# Umbilical104.net
KiCad netlist of a schematic drawn in Altium Designer
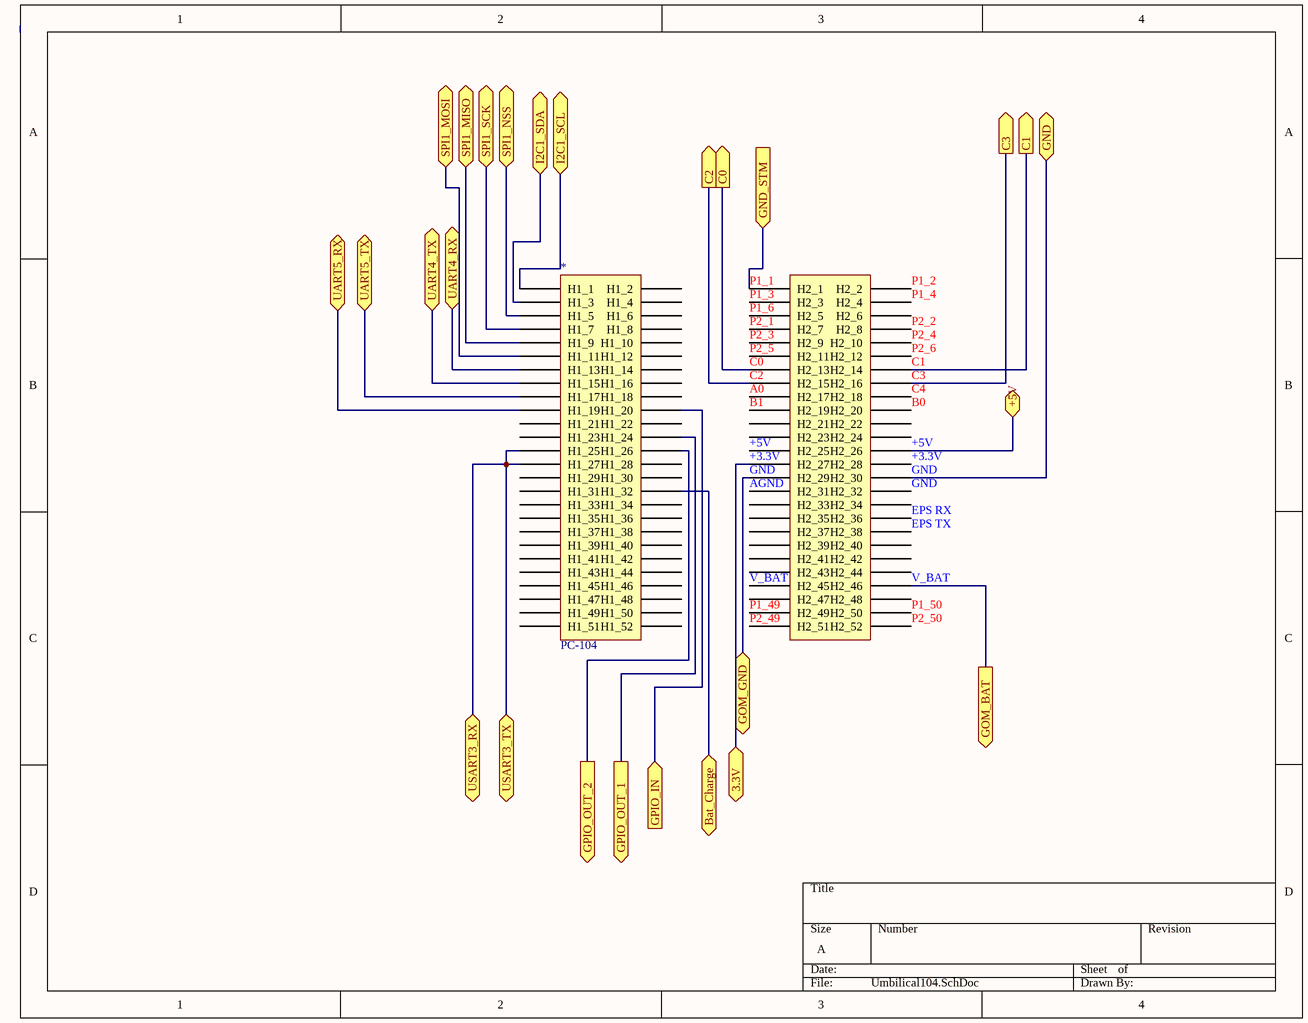
[diagram p0: Umbilical104.SchDoc]

(export (version "E")
  (design (tool "Eeschema 10.0.6"))
  (components
    (comp (ref "*")
      (value "PC-104")
      (footprint "PC-104FOOTPRINT")
      (libsource (lib "AdapterBoard") (part "PC-104"))
    )
  )
  (nets
    (net (code "1") (name "/+3.3V") (class "Default")
      (node (ref "*") (pin "H2_27") (pinfunction "H2_27_H2_27") (pintype "passive"))
      (node (ref "*") (pin "H2_28") (pinfunction "H2_28_H2_28") (pintype "passive"))
    )
    (net (code "2") (name "/+5V") (class "Default")
      (node (ref "*") (pin "H2_25") (pinfunction "H2_25_H2_25") (pintype "passive"))
      (node (ref "*") (pin "H2_26") (pinfunction "H2_26_H2_26") (pintype "passive"))
    )
    (net (code "3") (name "/A0") (class "Default")
      (node (ref "*") (pin "H2_17") (pinfunction "H2_17_H2_17") (pintype "passive"))
    )
    (net (code "4") (name "/AGND") (class "Default")
      (node (ref "*") (pin "H2_31") (pinfunction "H2_31_H2_31") (pintype "passive"))
    )
    (net (code "5") (name "/B0") (class "Default")
      (node (ref "*") (pin "H2_20") (pinfunction "H2_20_H2_20") (pintype "passive"))
    )
    (net (code "6") (name "/B1") (class "Default")
      (node (ref "*") (pin "H2_19") (pinfunction "H2_19_H2_19") (pintype "passive"))
    )
    (net (code "7") (name "/Bat_Charge") (class "Default")
      (node (ref "*") (pin "H1_32") (pinfunction "H1_32_H1_32") (pintype "passive"))
    )
    (net (code "8") (name "/C0") (class "Default")
      (node (ref "*") (pin "H2_13") (pinfunction "H2_13_H2_13") (pintype "passive"))
    )
    (net (code "9") (name "/C1") (class "Default")
      (node (ref "*") (pin "H2_14") (pinfunction "H2_14_H2_14") (pintype "passive"))
    )
    (net (code "10") (name "/C2") (class "Default")
      (node (ref "*") (pin "H2_15") (pinfunction "H2_15_H2_15") (pintype "passive"))
    )
    (net (code "11") (name "/C3") (class "Default")
      (node (ref "*") (pin "H2_16") (pinfunction "H2_16_H2_16") (pintype "passive"))
    )
    (net (code "12") (name "/C4") (class "Default")
      (node (ref "*") (pin "H2_18") (pinfunction "H2_18_H2_18") (pintype "passive"))
    )
    (net (code "13") (name "/EPS RX") (class "Default")
      (node (ref "*") (pin "H2_36") (pinfunction "H2_36_H2_36") (pintype "passive"))
    )
    (net (code "14") (name "/EPS TX") (class "Default")
      (node (ref "*") (pin "H2_38") (pinfunction "H2_38_H2_38") (pintype "passive"))
    )
    (net (code "15") (name "/GND") (class "Default")
      (node (ref "*") (pin "H2_29") (pinfunction "H2_29_H2_29") (pintype "passive"))
      (node (ref "*") (pin "H2_30") (pinfunction "H2_30_H2_30") (pintype "passive"))
      (node (ref "*") (pin "H2_32") (pinfunction "H2_32_H2_32") (pintype "passive"))
    )
    (net (code "16") (name "/GPIO_IN") (class "Default")
      (node (ref "*") (pin "H1_20") (pinfunction "H1_20_H1_20") (pintype "passive"))
    )
    (net (code "17") (name "/GPIO_OUT_1") (class "Default")
      (node (ref "*") (pin "H1_24") (pinfunction "H1_24_H1_24") (pintype "passive"))
    )
    (net (code "18") (name "/GPIO_OUT_2") (class "Default")
      (node (ref "*") (pin "H1_26") (pinfunction "H1_26_H1_26") (pintype "passive"))
    )
    (net (code "19") (name "/I2C1_SCL") (class "Default")
      (node (ref "*") (pin "H1_1") (pinfunction "H1_1_H1_1") (pintype "passive"))
    )
    (net (code "20") (name "/I2C1_SDA") (class "Default")
      (node (ref "*") (pin "H1_3") (pinfunction "H1_3_H1_3") (pintype "passive"))
    )
    (net (code "21") (name "/P1_1") (class "Default")
      (node (ref "*") (pin "H2_1") (pinfunction "H2_1_H2_1") (pintype "passive"))
    )
    (net (code "22") (name "/P1_2") (class "Default")
      (node (ref "*") (pin "H2_2") (pinfunction "H2_2_H2_2") (pintype "passive"))
    )
    (net (code "23") (name "/P1_3") (class "Default")
      (node (ref "*") (pin "H2_3") (pinfunction "H2_3_H2_3") (pintype "passive"))
    )
    (net (code "24") (name "/P1_4") (class "Default")
      (node (ref "*") (pin "H2_4") (pinfunction "H2_4_H2_4") (pintype "passive"))
    )
    (net (code "25") (name "/P1_6") (class "Default")
      (node (ref "*") (pin "H2_5") (pinfunction "H2_5_H2_5") (pintype "passive"))
    )
    (net (code "26") (name "/P1_49") (class "Default")
      (node (ref "*") (pin "H2_49") (pinfunction "H2_49_H2_49") (pintype "passive"))
    )
    (net (code "27") (name "/P1_50") (class "Default")
      (node (ref "*") (pin "H2_50") (pinfunction "H2_50_H2_50") (pintype "passive"))
    )
    (net (code "28") (name "/P2_1") (class "Default")
      (node (ref "*") (pin "H2_7") (pinfunction "H2_7_H2_7") (pintype "passive"))
    )
    (net (code "29") (name "/P2_2") (class "Default")
      (node (ref "*") (pin "H2_8") (pinfunction "H2_8_H2_8") (pintype "passive"))
    )
    (net (code "30") (name "/P2_3") (class "Default")
      (node (ref "*") (pin "H2_9") (pinfunction "H2_9_H2_9") (pintype "passive"))
    )
    (net (code "31") (name "/P2_4") (class "Default")
      (node (ref "*") (pin "H2_10") (pinfunction "H2_10_H2_10") (pintype "passive"))
    )
    (net (code "32") (name "/P2_5") (class "Default")
      (node (ref "*") (pin "H2_11") (pinfunction "H2_11_H2_11") (pintype "passive"))
    )
    (net (code "33") (name "/P2_6") (class "Default")
      (node (ref "*") (pin "H2_12") (pinfunction "H2_12_H2_12") (pintype "passive"))
    )
    (net (code "34") (name "/P2_49") (class "Default")
      (node (ref "*") (pin "H2_51") (pinfunction "H2_51_H2_51") (pintype "passive"))
    )
    (net (code "35") (name "/P2_50") (class "Default")
      (node (ref "*") (pin "H2_52") (pinfunction "H2_52_H2_52") (pintype "passive"))
    )
    (net (code "36") (name "/SPI1_MISO") (class "Default")
      (node (ref "*") (pin "H1_9") (pinfunction "H1_9_H1_9") (pintype "passive"))
    )
    (net (code "37") (name "/SPI1_MOSI") (class "Default")
      (node (ref "*") (pin "H1_11") (pinfunction "H1_11_H1_11") (pintype "passive"))
    )
    (net (code "38") (name "/SPI1_NSS") (class "Default")
      (node (ref "*") (pin "H1_5") (pinfunction "H1_5_H1_5") (pintype "passive"))
    )
    (net (code "39") (name "/SPI1_SCK") (class "Default")
      (node (ref "*") (pin "H1_7") (pinfunction "H1_7_H1_7") (pintype "passive"))
    )
    (net (code "40") (name "/UART4_RX") (class "Default")
      (node (ref "*") (pin "H1_13") (pinfunction "H1_13_H1_13") (pintype "passive"))
    )
    (net (code "41") (name "/UART4_TX") (class "Default")
      (node (ref "*") (pin "H1_15") (pinfunction "H1_15_H1_15") (pintype "passive"))
    )
    (net (code "42") (name "/UART5_RX") (class "Default")
      (node (ref "*") (pin "H1_19") (pinfunction "H1_19_H1_19") (pintype "passive"))
    )
    (net (code "43") (name "/UART5_TX") (class "Default")
      (node (ref "*") (pin "H1_17") (pinfunction "H1_17_H1_17") (pintype "passive"))
    )
    (net (code "44") (name "/USART3_RX") (class "Default")
      (node (ref "*") (pin "H1_25") (pinfunction "H1_25_H1_25") (pintype "passive"))
      (node (ref "*") (pin "H1_27") (pinfunction "H1_27_H1_27") (pintype "passive"))
    )
    (net (code "45") (name "/V_BAT") (class "Default")
      (node (ref "*") (pin "H2_45") (pinfunction "H2_45_H2_45") (pintype "passive"))
      (node (ref "*") (pin "H2_46") (pinfunction "H2_46_H2_46") (pintype "passive"))
    )
    (net (code "46") (name "unconnected-(*-PadH1_2)") (class "Default")
      (node (ref "*") (pin "H1_2") (pinfunction "H1_2_H1_2") (pintype "passive"))
    )
    (net (code "47") (name "unconnected-(*-PadH1_4)") (class "Default")
      (node (ref "*") (pin "H1_4") (pinfunction "H1_4_H1_4") (pintype "passive"))
    )
    (net (code "48") (name "unconnected-(*-PadH1_6)") (class "Default")
      (node (ref "*") (pin "H1_6") (pinfunction "H1_6_H1_6") (pintype "passive"))
    )
    (net (code "49") (name "unconnected-(*-PadH1_8)") (class "Default")
      (node (ref "*") (pin "H1_8") (pinfunction "H1_8_H1_8") (pintype "passive"))
    )
    (net (code "50") (name "unconnected-(*-PadH1_10)") (class "Default")
      (node (ref "*") (pin "H1_10") (pinfunction "H1_10_H1_10") (pintype "passive"))
    )
    (net (code "51") (name "unconnected-(*-PadH1_12)") (class "Default")
      (node (ref "*") (pin "H1_12") (pinfunction "H1_12_H1_12") (pintype "passive"))
    )
    (net (code "52") (name "unconnected-(*-PadH1_14)") (class "Default")
      (node (ref "*") (pin "H1_14") (pinfunction "H1_14_H1_14") (pintype "passive"))
    )
    (net (code "53") (name "unconnected-(*-PadH1_16)") (class "Default")
      (node (ref "*") (pin "H1_16") (pinfunction "H1_16_H1_16") (pintype "passive"))
    )
    (net (code "54") (name "unconnected-(*-PadH1_18)") (class "Default")
      (node (ref "*") (pin "H1_18") (pinfunction "H1_18_H1_18") (pintype "passive"))
    )
    (net (code "55") (name "unconnected-(*-PadH1_21)") (class "Default")
      (node (ref "*") (pin "H1_21") (pinfunction "H1_21_H1_21") (pintype "passive"))
    )
    (net (code "56") (name "unconnected-(*-PadH1_22)") (class "Default")
      (node (ref "*") (pin "H1_22") (pinfunction "H1_22_H1_22") (pintype "passive"))
    )
    (net (code "57") (name "unconnected-(*-PadH1_23)") (class "Default")
      (node (ref "*") (pin "H1_23") (pinfunction "H1_23_H1_23") (pintype "passive"))
    )
    (net (code "58") (name "unconnected-(*-PadH1_28)") (class "Default")
      (node (ref "*") (pin "H1_28") (pinfunction "H1_28_H1_28") (pintype "passive"))
    )
    (net (code "59") (name "unconnected-(*-PadH1_29)") (class "Default")
      (node (ref "*") (pin "H1_29") (pinfunction "H1_29_H1_29") (pintype "passive"))
    )
    (net (code "60") (name "unconnected-(*-PadH1_30)") (class "Default")
      (node (ref "*") (pin "H1_30") (pinfunction "H1_30_H1_30") (pintype "passive"))
    )
    (net (code "61") (name "unconnected-(*-PadH1_31)") (class "Default")
      (node (ref "*") (pin "H1_31") (pinfunction "H1_31_H1_31") (pintype "passive"))
    )
    (net (code "62") (name "unconnected-(*-PadH1_33)") (class "Default")
      (node (ref "*") (pin "H1_33") (pinfunction "H1_33_H1_33") (pintype "passive"))
    )
    (net (code "63") (name "unconnected-(*-PadH1_34)") (class "Default")
      (node (ref "*") (pin "H1_34") (pinfunction "H1_34_H1_34") (pintype "passive"))
    )
    (net (code "64") (name "unconnected-(*-PadH1_35)") (class "Default")
      (node (ref "*") (pin "H1_35") (pinfunction "H1_35_H1_35") (pintype "passive"))
    )
    (net (code "65") (name "unconnected-(*-PadH1_36)") (class "Default")
      (node (ref "*") (pin "H1_36") (pinfunction "H1_36_H1_36") (pintype "passive"))
    )
    (net (code "66") (name "unconnected-(*-PadH1_37)") (class "Default")
      (node (ref "*") (pin "H1_37") (pinfunction "H1_37_H1_37") (pintype "passive"))
    )
    (net (code "67") (name "unconnected-(*-PadH1_38)") (class "Default")
      (node (ref "*") (pin "H1_38") (pinfunction "H1_38_H1_38") (pintype "passive"))
    )
    (net (code "68") (name "unconnected-(*-PadH1_39)") (class "Default")
      (node (ref "*") (pin "H1_39") (pinfunction "H1_39_H1_39") (pintype "passive"))
    )
    (net (code "69") (name "unconnected-(*-PadH1_40)") (class "Default")
      (node (ref "*") (pin "H1_40") (pinfunction "H1_40_H1_40") (pintype "passive"))
    )
    (net (code "70") (name "unconnected-(*-PadH1_41)") (class "Default")
      (node (ref "*") (pin "H1_41") (pinfunction "H1_41_H1_41") (pintype "passive"))
    )
    (net (code "71") (name "unconnected-(*-PadH1_42)") (class "Default")
      (node (ref "*") (pin "H1_42") (pinfunction "H1_42_H1_42") (pintype "passive"))
    )
    (net (code "72") (name "unconnected-(*-PadH1_43)") (class "Default")
      (node (ref "*") (pin "H1_43") (pinfunction "H1_43_H1_43") (pintype "passive"))
    )
    (net (code "73") (name "unconnected-(*-PadH1_44)") (class "Default")
      (node (ref "*") (pin "H1_44") (pinfunction "H1_44_H1_44") (pintype "passive"))
    )
    (net (code "74") (name "unconnected-(*-PadH1_45)") (class "Default")
      (node (ref "*") (pin "H1_45") (pinfunction "H1_45_H1_45") (pintype "passive"))
    )
    (net (code "75") (name "unconnected-(*-PadH1_46)") (class "Default")
      (node (ref "*") (pin "H1_46") (pinfunction "H1_46_H1_46") (pintype "passive"))
    )
    (net (code "76") (name "unconnected-(*-PadH1_47)") (class "Default")
      (node (ref "*") (pin "H1_47") (pinfunction "H1_47_H1_47") (pintype "passive"))
    )
    (net (code "77") (name "unconnected-(*-PadH1_48)") (class "Default")
      (node (ref "*") (pin "H1_48") (pinfunction "H1_48_H1_48") (pintype "passive"))
    )
    (net (code "78") (name "unconnected-(*-PadH1_49)") (class "Default")
      (node (ref "*") (pin "H1_49") (pinfunction "H1_49_H1_49") (pintype "passive"))
    )
    (net (code "79") (name "unconnected-(*-PadH1_50)") (class "Default")
      (node (ref "*") (pin "H1_50") (pinfunction "H1_50_H1_50") (pintype "passive"))
    )
    (net (code "80") (name "unconnected-(*-PadH1_51)") (class "Default")
      (node (ref "*") (pin "H1_51") (pinfunction "H1_51_H1_51") (pintype "passive"))
    )
    (net (code "81") (name "unconnected-(*-PadH1_52)") (class "Default")
      (node (ref "*") (pin "H1_52") (pinfunction "H1_52_H1_52") (pintype "passive"))
    )
    (net (code "82") (name "unconnected-(*-PadH2_6)") (class "Default")
      (node (ref "*") (pin "H2_6") (pinfunction "H2_6_H2_6") (pintype "passive"))
    )
    (net (code "83") (name "unconnected-(*-PadH2_21)") (class "Default")
      (node (ref "*") (pin "H2_21") (pinfunction "H2_21_H2_21") (pintype "passive"))
    )
    (net (code "84") (name "unconnected-(*-PadH2_22)") (class "Default")
      (node (ref "*") (pin "H2_22") (pinfunction "H2_22_H2_22") (pintype "passive"))
    )
    (net (code "85") (name "unconnected-(*-PadH2_23)") (class "Default")
      (node (ref "*") (pin "H2_23") (pinfunction "H2_23_H2_23") (pintype "passive"))
    )
    (net (code "86") (name "unconnected-(*-PadH2_24)") (class "Default")
      (node (ref "*") (pin "H2_24") (pinfunction "H2_24_H2_24") (pintype "passive"))
    )
    (net (code "87") (name "unconnected-(*-PadH2_33)") (class "Default")
      (node (ref "*") (pin "H2_33") (pinfunction "H2_33_H2_33") (pintype "passive"))
    )
    (net (code "88") (name "unconnected-(*-PadH2_34)") (class "Default")
      (node (ref "*") (pin "H2_34") (pinfunction "H2_34_H2_34") (pintype "passive"))
    )
    (net (code "89") (name "unconnected-(*-PadH2_35)") (class "Default")
      (node (ref "*") (pin "H2_35") (pinfunction "H2_35_H2_35") (pintype "passive"))
    )
    (net (code "90") (name "unconnected-(*-PadH2_37)") (class "Default")
      (node (ref "*") (pin "H2_37") (pinfunction "H2_37_H2_37") (pintype "passive"))
    )
    (net (code "91") (name "unconnected-(*-PadH2_39)") (class "Default")
      (node (ref "*") (pin "H2_39") (pinfunction "H2_39_H2_39") (pintype "passive"))
    )
    (net (code "92") (name "unconnected-(*-PadH2_40)") (class "Default")
      (node (ref "*") (pin "H2_40") (pinfunction "H2_40_H2_40") (pintype "passive"))
    )
    (net (code "93") (name "unconnected-(*-PadH2_41)") (class "Default")
      (node (ref "*") (pin "H2_41") (pinfunction "H2_41_H2_41") (pintype "passive"))
    )
    (net (code "94") (name "unconnected-(*-PadH2_42)") (class "Default")
      (node (ref "*") (pin "H2_42") (pinfunction "H2_42_H2_42") (pintype "passive"))
    )
    (net (code "95") (name "unconnected-(*-PadH2_43)") (class "Default")
      (node (ref "*") (pin "H2_43") (pinfunction "H2_43_H2_43") (pintype "passive"))
    )
    (net (code "96") (name "unconnected-(*-PadH2_44)") (class "Default")
      (node (ref "*") (pin "H2_44") (pinfunction "H2_44_H2_44") (pintype "passive"))
    )
    (net (code "97") (name "unconnected-(*-PadH2_47)") (class "Default")
      (node (ref "*") (pin "H2_47") (pinfunction "H2_47_H2_47") (pintype "passive"))
    )
    (net (code "98") (name "unconnected-(*-PadH2_48)") (class "Default")
      (node (ref "*") (pin "H2_48") (pinfunction "H2_48_H2_48") (pintype "passive"))
    )
  )
)
